# EEZ_DIB_BP3C_r1B5.net
KiCad netlist of a schematic drawn in EAGLE
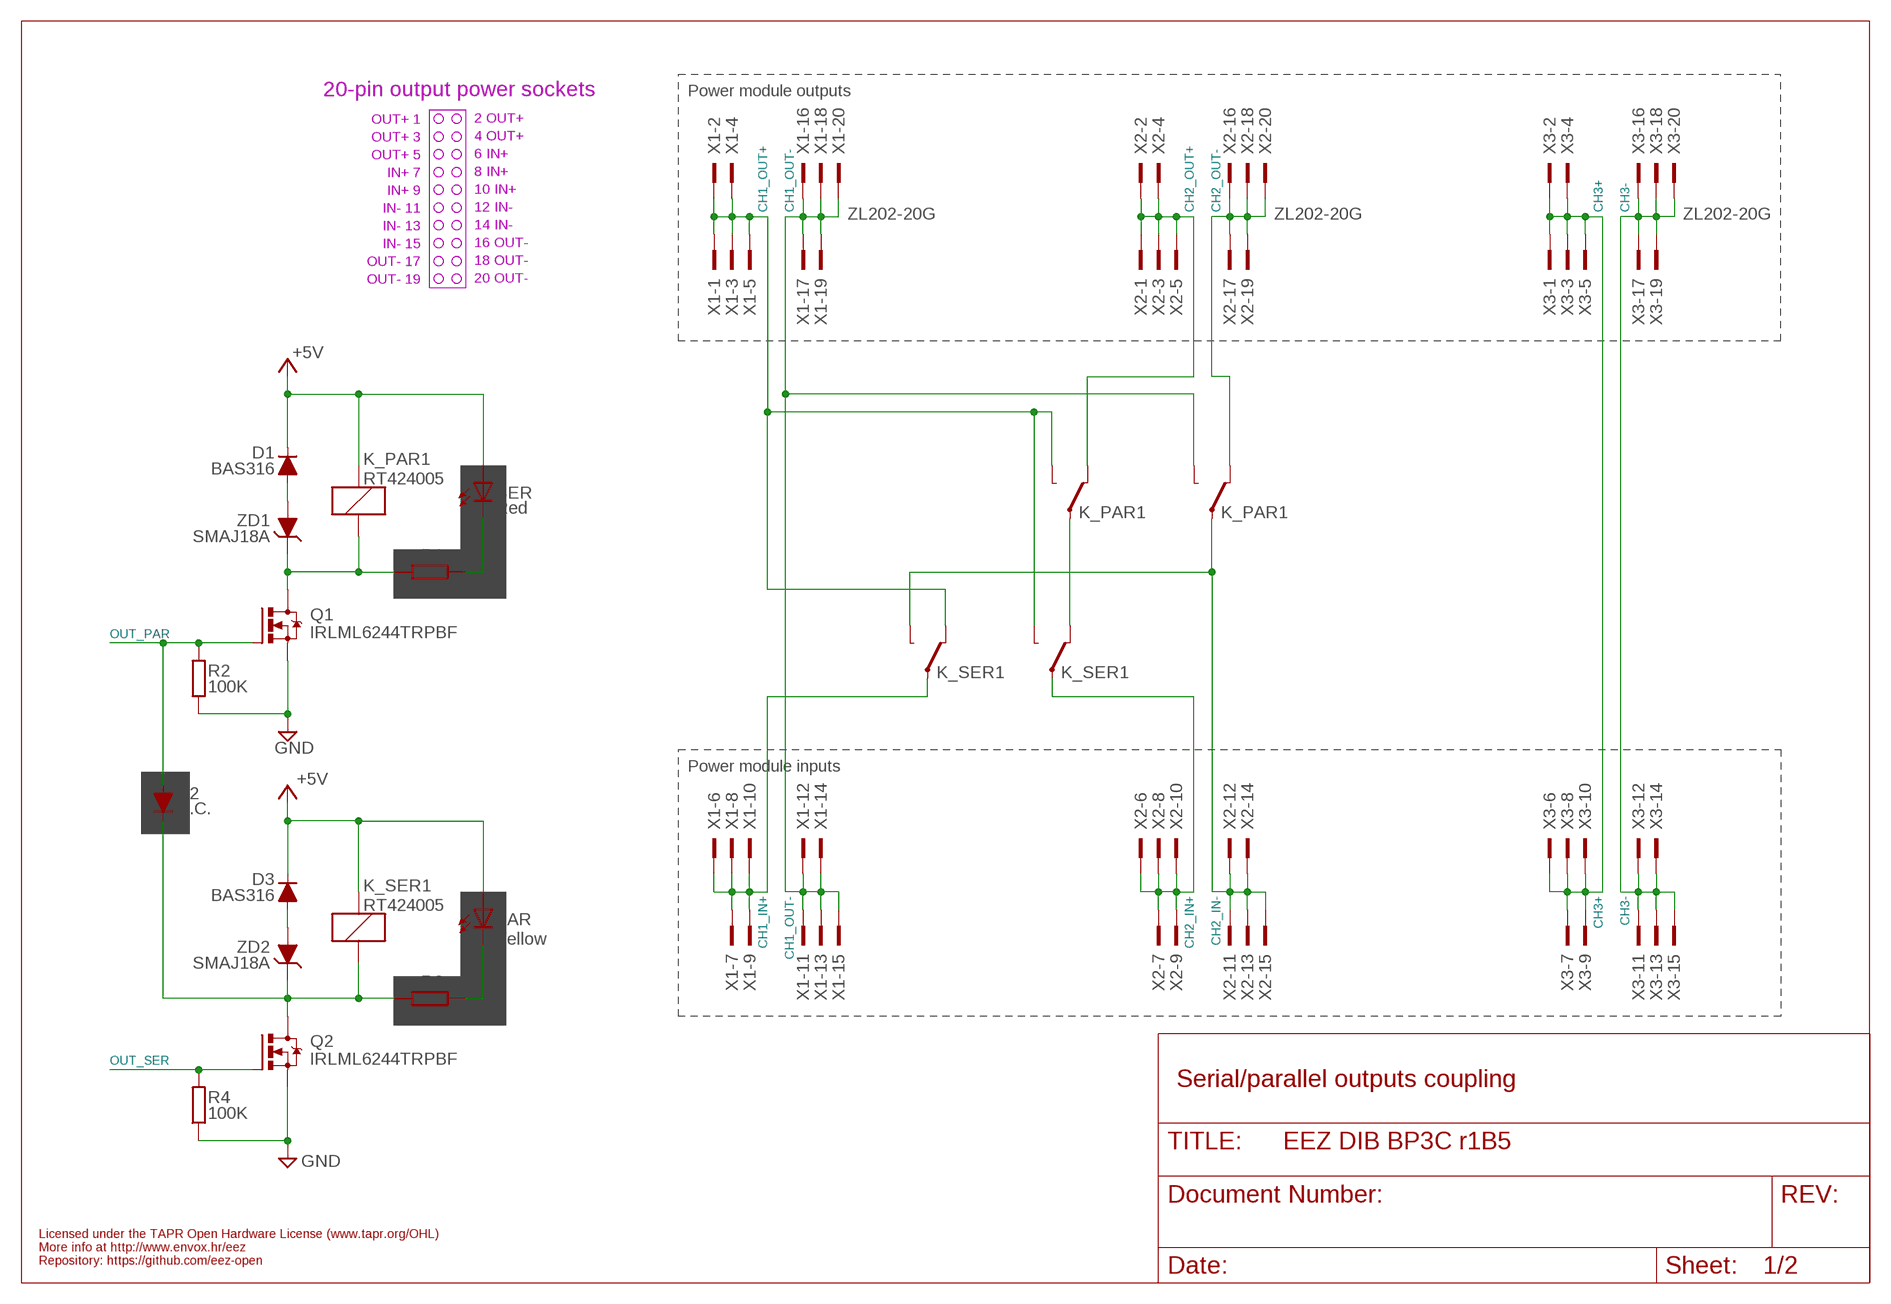
[diagram p0: schematic, sheet 1]
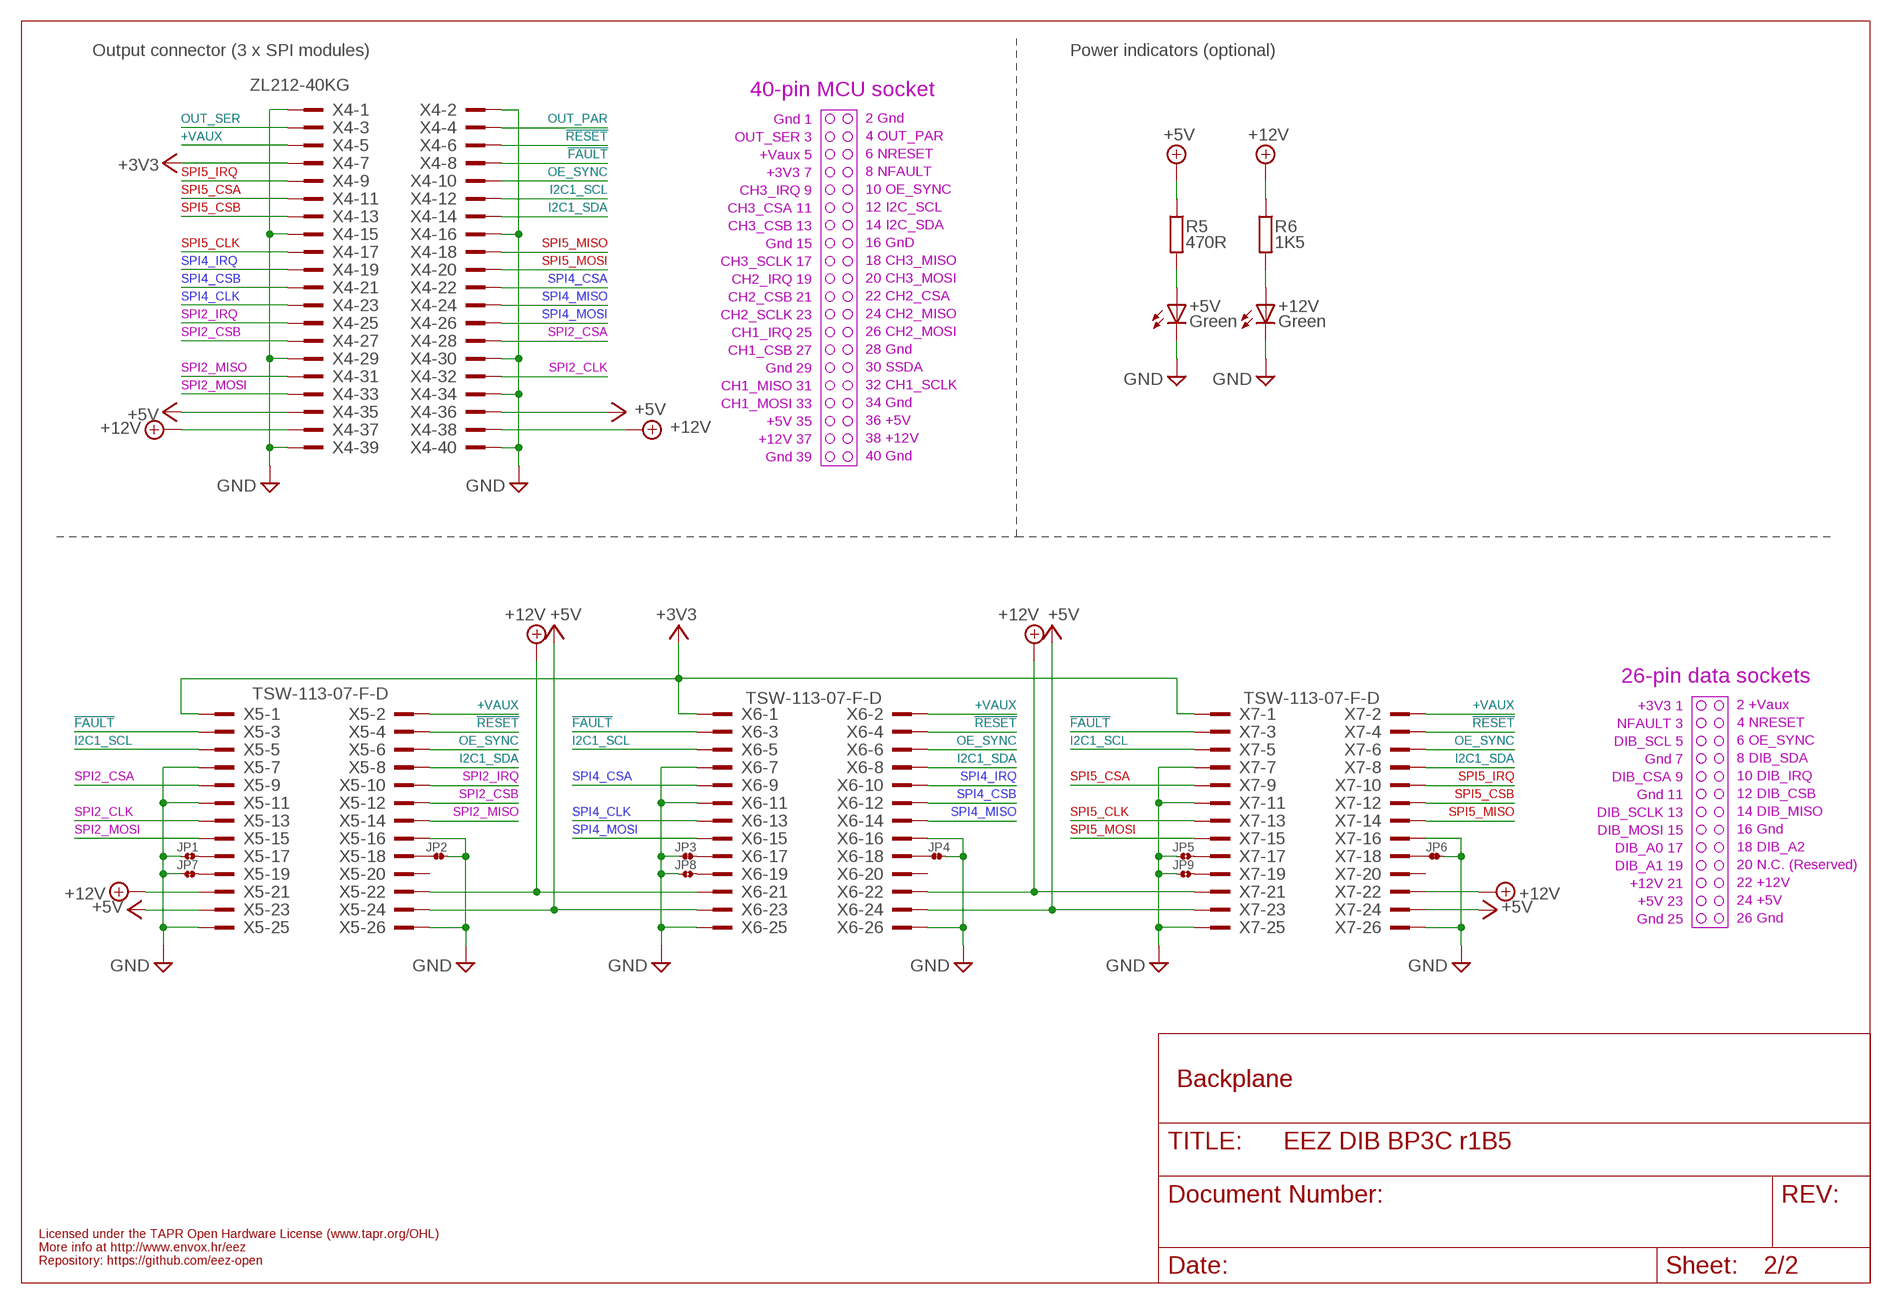
[diagram p1: schematic, sheet 2]

(export (version "E")
  (design (tool "Eeschema 10.0.6"))
  (components
    (comp (ref "D1")
      (value "BAS316")
      (footprint "eagle-import:SOD323-R")
      (libsource (lib "eagle-import") (part "DIODESOD323R"))
    )
    (comp (ref "D2")
      (value "N.C.")
      (footprint "eagle-import:SOD323-R")
      (libsource (lib "eagle-import") (part "DIODESOD323R"))
    )
    (comp (ref "D3")
      (value "BAS316")
      (footprint "eagle-import:SOD323-R")
      (libsource (lib "eagle-import") (part "DIODESOD323R"))
    )
    (comp (ref "K_PAR1")
      (value "RT424005")
      (footprint "eagle-import:RT-C_016A5_ROUND")
      (libsource (lib "eagle-import") (part "RELAY_RT314012-2"))
    )
    (comp (ref "K_SER1")
      (value "RT424005")
      (footprint "eagle-import:RT-C_016A5_ROUND")
      (libsource (lib "eagle-import") (part "RELAY_RT314012-2"))
    )
    (comp (ref "PAR")
      (value "Yellow")
      (footprint "eagle-import:LED_0805")
      (libsource (lib "eagle-import") (part "LED0805"))
    )
    (comp (ref "Q1")
      (value "IRLML6244TRPBF")
      (footprint "eagle-import:SOT103P240X110-3N")
      (fields
        (field (name "MPN") "2N7002-7-F")
        (field (name "MPN_1") "2N7002-7-F")
        (field (name "OC_FARNELL") "1713823")
        (field (name "OC_NEWARK") "25R5679")
        (field (name "PACKAGE") "SOT-23-3")
        (field (name "SUPPLIER") "DIODES INC.")
      )
      (libsource (lib "eagle-import") (part "2N7002"))
    )
    (comp (ref "Q2")
      (value "IRLML6244TRPBF")
      (footprint "eagle-import:SOT103P240X110-3N")
      (fields
        (field (name "MPN") "2N7002-7-F")
        (field (name "MPN_1") "2N7002-7-F")
        (field (name "OC_FARNELL") "1713823")
        (field (name "OC_NEWARK") "25R5679")
        (field (name "PACKAGE") "SOT-23-3")
        (field (name "SUPPLIER") "DIODES INC.")
      )
      (libsource (lib "eagle-import") (part "2N7002"))
    )
    (comp (ref "R1")
      (value "330R")
      (footprint "eagle-import:R0805")
      (libsource (lib "eagle-import") (part "R-EU_R0805"))
    )
    (comp (ref "R2")
      (value "100K")
      (footprint "eagle-import:R0805")
      (libsource (lib "eagle-import") (part "R-EU_R0805"))
    )
    (comp (ref "R3")
      (value "330R")
      (footprint "eagle-import:R0805")
      (libsource (lib "eagle-import") (part "R-EU_R0805"))
    )
    (comp (ref "R4")
      (value "100K")
      (footprint "eagle-import:R0805")
      (libsource (lib "eagle-import") (part "R-EU_R0805"))
    )
    (comp (ref "SER")
      (value "Red")
      (footprint "eagle-import:LED_0805")
      (libsource (lib "eagle-import") (part "LED0805"))
    )
    (comp (ref "X1")
      (value "ZL202-20G")
      (footprint "eagle-import:DS1021-2_10SF11")
      (libsource (lib "eagle-import") (part "DS1021-210SF11"))
    )
    (comp (ref "X2")
      (value "ZL202-20G")
      (footprint "eagle-import:DS1021-2_10SF11")
      (libsource (lib "eagle-import") (part "DS1021-210SF11"))
    )
    (comp (ref "X3")
      (value "ZL202-20G")
      (footprint "eagle-import:DS1021-2_10SF11")
      (libsource (lib "eagle-import") (part "DS1021-210SF11"))
    )
    (comp (ref "ZD1")
      (value "SMAJ18A")
      (footprint "eagle-import:DO214AC")
      (libsource (lib "eagle-import") (part "PSMAXX"))
    )
    (comp (ref "ZD2")
      (value "SMAJ18A")
      (footprint "eagle-import:DO214AC")
      (libsource (lib "eagle-import") (part "PSMAXX"))
    )
    (comp (ref "+5V")
      (value "Green")
      (footprint "eagle-import:LED_0805")
      (libsource (lib "eagle-import") (part "LED0805"))
    )
    (comp (ref "+12V")
      (value "Green")
      (footprint "eagle-import:LED_0805")
      (libsource (lib "eagle-import") (part "LED0805"))
    )
    (comp (ref "JP1")
      (value "JP2-CUT")
      (footprint "eagle-import:JP2-CUT")
      (libsource (lib "eagle-import") (part "JP2-CUT"))
    )
    (comp (ref "JP2")
      (value "JP2-NOCUT")
      (footprint "eagle-import:JP2-NOCUT")
      (libsource (lib "eagle-import") (part "JP2-NOCUT"))
    )
    (comp (ref "JP3")
      (value "JP2-NOCUT")
      (footprint "eagle-import:JP2-NOCUT")
      (libsource (lib "eagle-import") (part "JP2-NOCUT"))
    )
    (comp (ref "JP4")
      (value "JP2-NOCUT")
      (footprint "eagle-import:JP2-NOCUT")
      (libsource (lib "eagle-import") (part "JP2-NOCUT"))
    )
    (comp (ref "JP5")
      (value "JP2-CUT")
      (footprint "eagle-import:JP2-CUT")
      (libsource (lib "eagle-import") (part "JP2-CUT"))
    )
    (comp (ref "JP6")
      (value "JP2-NOCUT")
      (footprint "eagle-import:JP2-NOCUT")
      (libsource (lib "eagle-import") (part "JP2-NOCUT"))
    )
    (comp (ref "JP7")
      (value "JP2-NOCUT")
      (footprint "eagle-import:JP2-NOCUT")
      (libsource (lib "eagle-import") (part "JP2-NOCUT"))
    )
    (comp (ref "JP8")
      (value "JP2-CUT")
      (footprint "eagle-import:JP2-CUT")
      (libsource (lib "eagle-import") (part "JP2-CUT"))
    )
    (comp (ref "JP9")
      (value "JP2-CUT")
      (footprint "eagle-import:JP2-CUT")
      (libsource (lib "eagle-import") (part "JP2-CUT"))
    )
    (comp (ref "R5")
      (value "470R")
      (footprint "eagle-import:R0805")
      (libsource (lib "eagle-import") (part "R-EU_R0805"))
    )
    (comp (ref "R6")
      (value "1K5")
      (footprint "eagle-import:R0805")
      (libsource (lib "eagle-import") (part "R-EU_R0805"))
    )
    (comp (ref "X4")
      (value "ZL212-40KG")
      (footprint "eagle-import:ZL212-40KG")
      (libsource (lib "eagle-import") (part "ZL212-40KG"))
    )
    (comp (ref "X5")
      (value "TSW-113-07-F-D")
      (footprint "eagle-import:TSW-113-07-F-D")
      (libsource (lib "eagle-import") (part "TSW-113-07-F-D"))
    )
    (comp (ref "X6")
      (value "TSW-113-07-F-D")
      (footprint "eagle-import:TSW-113-07-F-D")
      (libsource (lib "eagle-import") (part "TSW-113-07-F-D"))
    )
    (comp (ref "X7")
      (value "TSW-113-07-F-D")
      (footprint "eagle-import:TSW-113-07-F-D")
      (libsource (lib "eagle-import") (part "TSW-113-07-F-D"))
    )
  )
  (nets
    (net (code "1") (name "+3V3") (class "Default")
      (node (ref "X4") (pin "7") (pinfunction "1_7") (pintype "passive"))
      (node (ref "X5") (pin "1") (pinfunction "1_1") (pintype "passive"))
      (node (ref "X6") (pin "1") (pinfunction "1_1") (pintype "passive"))
      (node (ref "X7") (pin "1") (pinfunction "1_1") (pintype "passive"))
    )
    (net (code "2") (name "+5V") (class "Default")
      (node (ref "D1") (pin "C") (pinfunction "C_C") (pintype "passive"))
      (node (ref "D3") (pin "C") (pinfunction "C_C") (pintype "passive"))
      (node (ref "K_PAR1") (pin "A2") (pinfunction "C1_A2") (pintype "passive"))
      (node (ref "K_SER1") (pin "A2") (pinfunction "C1_A2") (pintype "passive"))
      (node (ref "PAR") (pin "A") (pinfunction "A_A") (pintype "passive"))
      (node (ref "R5") (pin "1") (pinfunction "1_1") (pintype "passive"))
      (node (ref "SER") (pin "A") (pinfunction "A_A") (pintype "passive"))
      (node (ref "X4") (pin "35") (pinfunction "1_35") (pintype "passive"))
      (node (ref "X4") (pin "36") (pinfunction "1_36") (pintype "passive"))
      (node (ref "X5") (pin "23") (pinfunction "1_23") (pintype "passive"))
      (node (ref "X5") (pin "24") (pinfunction "1_24") (pintype "passive"))
      (node (ref "X6") (pin "23") (pinfunction "1_23") (pintype "passive"))
      (node (ref "X6") (pin "24") (pinfunction "1_24") (pintype "passive"))
      (node (ref "X7") (pin "23") (pinfunction "1_23") (pintype "passive"))
      (node (ref "X7") (pin "24") (pinfunction "1_24") (pintype "passive"))
    )
    (net (code "3") (name "+12V") (class "Default")
      (node (ref "R6") (pin "1") (pinfunction "1_1") (pintype "passive"))
      (node (ref "X4") (pin "37") (pinfunction "1_37") (pintype "passive"))
      (node (ref "X4") (pin "38") (pinfunction "1_38") (pintype "passive"))
      (node (ref "X5") (pin "21") (pinfunction "1_21") (pintype "passive"))
      (node (ref "X5") (pin "22") (pinfunction "1_22") (pintype "passive"))
      (node (ref "X6") (pin "21") (pinfunction "1_21") (pintype "passive"))
      (node (ref "X6") (pin "22") (pinfunction "1_22") (pintype "passive"))
      (node (ref "X7") (pin "21") (pinfunction "1_21") (pintype "passive"))
      (node (ref "X7") (pin "22") (pinfunction "1_22") (pintype "passive"))
    )
    (net (code "4") (name "+VAUX") (class "Default")
      (node (ref "X4") (pin "5") (pinfunction "1_5") (pintype "passive"))
      (node (ref "X5") (pin "2") (pinfunction "1_2") (pintype "passive"))
      (node (ref "X6") (pin "2") (pinfunction "1_2") (pintype "passive"))
      (node (ref "X7") (pin "2") (pinfunction "1_2") (pintype "passive"))
    )
    (net (code "5") (name "CH1_IN+") (class "Default")
      (node (ref "K_SER1") (pin "11A") (pinfunction "P_11A") (pintype "passive"))
      (node (ref "X1") (pin "10") (pinfunction "1_10") (pintype "passive"))
      (node (ref "X1") (pin "6") (pinfunction "1_6") (pintype "passive"))
      (node (ref "X1") (pin "7") (pinfunction "1_7") (pintype "passive"))
      (node (ref "X1") (pin "8") (pinfunction "1_8") (pintype "passive"))
      (node (ref "X1") (pin "9") (pinfunction "1_9") (pintype "passive"))
    )
    (net (code "6") (name "CH1_OUT+") (class "Default")
      (node (ref "K_PAR1") (pin "14A") (pinfunction "O_14A") (pintype "passive"))
      (node (ref "K_SER1") (pin "12A") (pinfunction "S_12A") (pintype "passive"))
      (node (ref "K_SER1") (pin "14B") (pinfunction "O_14B") (pintype "passive"))
      (node (ref "X1") (pin "1") (pinfunction "1_1") (pintype "passive"))
      (node (ref "X1") (pin "2") (pinfunction "1_2") (pintype "passive"))
      (node (ref "X1") (pin "3") (pinfunction "1_3") (pintype "passive"))
      (node (ref "X1") (pin "4") (pinfunction "1_4") (pintype "passive"))
      (node (ref "X1") (pin "5") (pinfunction "1_5") (pintype "passive"))
    )
    (net (code "7") (name "CH1_OUT-") (class "Default")
      (node (ref "K_PAR1") (pin "14B") (pinfunction "O_14B") (pintype "passive"))
      (node (ref "X1") (pin "11") (pinfunction "1_11") (pintype "passive"))
      (node (ref "X1") (pin "12") (pinfunction "1_12") (pintype "passive"))
      (node (ref "X1") (pin "13") (pinfunction "1_13") (pintype "passive"))
      (node (ref "X1") (pin "14") (pinfunction "1_14") (pintype "passive"))
      (node (ref "X1") (pin "15") (pinfunction "1_15") (pintype "passive"))
      (node (ref "X1") (pin "16") (pinfunction "1_16") (pintype "passive"))
      (node (ref "X1") (pin "17") (pinfunction "1_17") (pintype "passive"))
      (node (ref "X1") (pin "18") (pinfunction "1_18") (pintype "passive"))
      (node (ref "X1") (pin "19") (pinfunction "1_19") (pintype "passive"))
      (node (ref "X1") (pin "20") (pinfunction "1_20") (pintype "passive"))
    )
    (net (code "8") (name "CH2_IN+") (class "Default")
      (node (ref "K_SER1") (pin "11B") (pinfunction "P_11B") (pintype "passive"))
      (node (ref "X2") (pin "10") (pinfunction "1_10") (pintype "passive"))
      (node (ref "X2") (pin "6") (pinfunction "1_6") (pintype "passive"))
      (node (ref "X2") (pin "7") (pinfunction "1_7") (pintype "passive"))
      (node (ref "X2") (pin "8") (pinfunction "1_8") (pintype "passive"))
      (node (ref "X2") (pin "9") (pinfunction "1_9") (pintype "passive"))
    )
    (net (code "9") (name "CH2_IN-") (class "Default")
      (node (ref "K_PAR1") (pin "11B") (pinfunction "P_11B") (pintype "passive"))
      (node (ref "K_SER1") (pin "14A") (pinfunction "O_14A") (pintype "passive"))
      (node (ref "X2") (pin "11") (pinfunction "1_11") (pintype "passive"))
      (node (ref "X2") (pin "12") (pinfunction "1_12") (pintype "passive"))
      (node (ref "X2") (pin "13") (pinfunction "1_13") (pintype "passive"))
      (node (ref "X2") (pin "14") (pinfunction "1_14") (pintype "passive"))
      (node (ref "X2") (pin "15") (pinfunction "1_15") (pintype "passive"))
    )
    (net (code "10") (name "CH2_OUT+") (class "Default")
      (node (ref "K_PAR1") (pin "12A") (pinfunction "S_12A") (pintype "passive"))
      (node (ref "X2") (pin "1") (pinfunction "1_1") (pintype "passive"))
      (node (ref "X2") (pin "2") (pinfunction "1_2") (pintype "passive"))
      (node (ref "X2") (pin "3") (pinfunction "1_3") (pintype "passive"))
      (node (ref "X2") (pin "4") (pinfunction "1_4") (pintype "passive"))
      (node (ref "X2") (pin "5") (pinfunction "1_5") (pintype "passive"))
    )
    (net (code "11") (name "CH2_OUT-") (class "Default")
      (node (ref "K_PAR1") (pin "12B") (pinfunction "S_12B") (pintype "passive"))
      (node (ref "X2") (pin "16") (pinfunction "1_16") (pintype "passive"))
      (node (ref "X2") (pin "17") (pinfunction "1_17") (pintype "passive"))
      (node (ref "X2") (pin "18") (pinfunction "1_18") (pintype "passive"))
      (node (ref "X2") (pin "19") (pinfunction "1_19") (pintype "passive"))
      (node (ref "X2") (pin "20") (pinfunction "1_20") (pintype "passive"))
    )
    (net (code "12") (name "CH3+") (class "Default")
      (node (ref "X3") (pin "1") (pinfunction "1_1") (pintype "passive"))
      (node (ref "X3") (pin "10") (pinfunction "1_10") (pintype "passive"))
      (node (ref "X3") (pin "2") (pinfunction "1_2") (pintype "passive"))
      (node (ref "X3") (pin "3") (pinfunction "1_3") (pintype "passive"))
      (node (ref "X3") (pin "4") (pinfunction "1_4") (pintype "passive"))
      (node (ref "X3") (pin "5") (pinfunction "1_5") (pintype "passive"))
      (node (ref "X3") (pin "6") (pinfunction "1_6") (pintype "passive"))
      (node (ref "X3") (pin "7") (pinfunction "1_7") (pintype "passive"))
      (node (ref "X3") (pin "8") (pinfunction "1_8") (pintype "passive"))
      (node (ref "X3") (pin "9") (pinfunction "1_9") (pintype "passive"))
    )
    (net (code "13") (name "CH3-") (class "Default")
      (node (ref "X3") (pin "11") (pinfunction "1_11") (pintype "passive"))
      (node (ref "X3") (pin "12") (pinfunction "1_12") (pintype "passive"))
      (node (ref "X3") (pin "13") (pinfunction "1_13") (pintype "passive"))
      (node (ref "X3") (pin "14") (pinfunction "1_14") (pintype "passive"))
      (node (ref "X3") (pin "15") (pinfunction "1_15") (pintype "passive"))
      (node (ref "X3") (pin "16") (pinfunction "1_16") (pintype "passive"))
      (node (ref "X3") (pin "17") (pinfunction "1_17") (pintype "passive"))
      (node (ref "X3") (pin "18") (pinfunction "1_18") (pintype "passive"))
      (node (ref "X3") (pin "19") (pinfunction "1_19") (pintype "passive"))
      (node (ref "X3") (pin "20") (pinfunction "1_20") (pintype "passive"))
    )
    (net (code "14") (name "GND") (class "Default")
      (node (ref "+12V") (pin "C") (pinfunction "C_C") (pintype "passive"))
      (node (ref "+5V") (pin "C") (pinfunction "C_C") (pintype "passive"))
      (node (ref "JP1") (pin "1") (pinfunction "1_1") (pintype "passive"))
      (node (ref "JP2") (pin "2") (pinfunction "2_2") (pintype "passive"))
      (node (ref "JP3") (pin "1") (pinfunction "1_1") (pintype "passive"))
      (node (ref "JP4") (pin "2") (pinfunction "2_2") (pintype "passive"))
      (node (ref "JP5") (pin "1") (pinfunction "1_1") (pintype "passive"))
      (node (ref "JP6") (pin "2") (pinfunction "2_2") (pintype "passive"))
      (node (ref "JP7") (pin "1") (pinfunction "1_1") (pintype "passive"))
      (node (ref "JP8") (pin "1") (pinfunction "1_1") (pintype "passive"))
      (node (ref "JP9") (pin "1") (pinfunction "1_1") (pintype "passive"))
      (node (ref "Q1") (pin "2") (pinfunction "S_2") (pintype "passive"))
      (node (ref "Q2") (pin "2") (pinfunction "S_2") (pintype "passive"))
      (node (ref "R2") (pin "1") (pinfunction "1_1") (pintype "passive"))
      (node (ref "R4") (pin "1") (pinfunction "1_1") (pintype "passive"))
      (node (ref "X4") (pin "1") (pinfunction "1_1") (pintype "passive"))
      (node (ref "X4") (pin "15") (pinfunction "1_15") (pintype "passive"))
      (node (ref "X4") (pin "16") (pinfunction "1_16") (pintype "passive"))
      (node (ref "X4") (pin "2") (pinfunction "1_2") (pintype "passive"))
      (node (ref "X4") (pin "29") (pinfunction "1_29") (pintype "passive"))
      (node (ref "X4") (pin "30") (pinfunction "1_30") (pintype "passive"))
      (node (ref "X4") (pin "34") (pinfunction "1_34") (pintype "passive"))
      (node (ref "X4") (pin "39") (pinfunction "1_39") (pintype "passive"))
      (node (ref "X4") (pin "40") (pinfunction "1_40") (pintype "passive"))
      (node (ref "X5") (pin "11") (pinfunction "1_11") (pintype "passive"))
      (node (ref "X5") (pin "16") (pinfunction "1_16") (pintype "passive"))
      (node (ref "X5") (pin "25") (pinfunction "1_25") (pintype "passive"))
      (node (ref "X5") (pin "26") (pinfunction "1_26") (pintype "passive"))
      (node (ref "X5") (pin "7") (pinfunction "1_7") (pintype "passive"))
      (node (ref "X6") (pin "11") (pinfunction "1_11") (pintype "passive"))
      (node (ref "X6") (pin "16") (pinfunction "1_16") (pintype "passive"))
      (node (ref "X6") (pin "25") (pinfunction "1_25") (pintype "passive"))
      (node (ref "X6") (pin "26") (pinfunction "1_26") (pintype "passive"))
      (node (ref "X6") (pin "7") (pinfunction "1_7") (pintype "passive"))
      (node (ref "X7") (pin "11") (pinfunction "1_11") (pintype "passive"))
      (node (ref "X7") (pin "16") (pinfunction "1_16") (pintype "passive"))
      (node (ref "X7") (pin "25") (pinfunction "1_25") (pintype "passive"))
      (node (ref "X7") (pin "26") (pinfunction "1_26") (pintype "passive"))
      (node (ref "X7") (pin "7") (pinfunction "1_7") (pintype "passive"))
    )
    (net (code "15") (name "I2C1_SCL") (class "Default")
      (node (ref "X4") (pin "12") (pinfunction "1_12") (pintype "passive"))
      (node (ref "X5") (pin "5") (pinfunction "1_5") (pintype "passive"))
      (node (ref "X6") (pin "5") (pinfunction "1_5") (pintype "passive"))
      (node (ref "X7") (pin "5") (pinfunction "1_5") (pintype "passive"))
    )
    (net (code "16") (name "I2C1_SDA") (class "Default")
      (node (ref "X4") (pin "14") (pinfunction "1_14") (pintype "passive"))
      (node (ref "X5") (pin "8") (pinfunction "1_8") (pintype "passive"))
      (node (ref "X6") (pin "8") (pinfunction "1_8") (pintype "passive"))
      (node (ref "X7") (pin "8") (pinfunction "1_8") (pintype "passive"))
    )
    (net (code "17") (name "Net-(+5V-PadA)") (class "Default")
      (node (ref "+5V") (pin "A") (pinfunction "A_A") (pintype "passive"))
      (node (ref "R5") (pin "2") (pinfunction "2_2") (pintype "passive"))
    )
    (net (code "18") (name "Net-(+12V-PadA)") (class "Default")
      (node (ref "+12V") (pin "A") (pinfunction "A_A") (pintype "passive"))
      (node (ref "R6") (pin "2") (pinfunction "2_2") (pintype "passive"))
    )
    (net (code "19") (name "Net-(D1-PadA)") (class "Default")
      (node (ref "D1") (pin "A") (pinfunction "A_A") (pintype "passive"))
      (node (ref "ZD1") (pin "A") (pinfunction "A_A") (pintype "passive"))
    )
    (net (code "20") (name "Net-(D3-PadA)") (class "Default")
      (node (ref "D3") (pin "A") (pinfunction "A_A") (pintype "passive"))
      (node (ref "ZD2") (pin "A") (pinfunction "A_A") (pintype "passive"))
    )
    (net (code "21") (name "Net-(K_PAR1A-P)") (class "Default")
      (node (ref "K_PAR1") (pin "11A") (pinfunction "P_11A") (pintype "passive"))
      (node (ref "K_SER1") (pin "12B") (pinfunction "S_12B") (pintype "passive"))
    )
    (net (code "22") (name "Net-(K_PAR1C-C2)") (class "Default")
      (node (ref "K_PAR1") (pin "A1") (pinfunction "C2_A1") (pintype "passive"))
      (node (ref "Q1") (pin "3") (pinfunction "D_3") (pintype "passive"))
      (node (ref "R1") (pin "2") (pinfunction "2_2") (pintype "passive"))
      (node (ref "ZD1") (pin "C") (pinfunction "C_C") (pintype "passive"))
    )
    (net (code "23") (name "Net-(K_SER1C-C2)") (class "Default")
      (node (ref "D2") (pin "C") (pinfunction "C_C") (pintype "passive"))
      (node (ref "K_SER1") (pin "A1") (pinfunction "C2_A1") (pintype "passive"))
      (node (ref "Q2") (pin "3") (pinfunction "D_3") (pintype "passive"))
      (node (ref "R3") (pin "2") (pinfunction "2_2") (pintype "passive"))
      (node (ref "ZD2") (pin "C") (pinfunction "C_C") (pintype "passive"))
    )
    (net (code "24") (name "Net-(PAR-PadC)") (class "Default")
      (node (ref "PAR") (pin "C") (pinfunction "C_C") (pintype "passive"))
      (node (ref "R3") (pin "1") (pinfunction "1_1") (pintype "passive"))
    )
    (net (code "25") (name "Net-(R1-Pad1)") (class "Default")
      (node (ref "R1") (pin "1") (pinfunction "1_1") (pintype "passive"))
      (node (ref "SER") (pin "C") (pinfunction "C_C") (pintype "passive"))
    )
    (net (code "26") (name "Net-(X5I-1)") (class "Default")
      (node (ref "JP1") (pin "2") (pinfunction "2_2") (pintype "passive"))
      (node (ref "X5") (pin "17") (pinfunction "1_17") (pintype "passive"))
    )
    (net (code "27") (name "Net-(X5J-1)") (class "Default")
      (node (ref "JP2") (pin "1") (pinfunction "1_1") (pintype "passive"))
      (node (ref "X5") (pin "18") (pinfunction "1_18") (pintype "passive"))
    )
    (net (code "28") (name "Net-(X5K-1)") (class "Default")
      (node (ref "JP7") (pin "2") (pinfunction "2_2") (pintype "passive"))
      (node (ref "X5") (pin "19") (pinfunction "1_19") (pintype "passive"))
    )
    (net (code "29") (name "Net-(X6I-1)") (class "Default")
      (node (ref "JP3") (pin "2") (pinfunction "2_2") (pintype "passive"))
      (node (ref "X6") (pin "17") (pinfunction "1_17") (pintype "passive"))
    )
    (net (code "30") (name "Net-(X6J-1)") (class "Default")
      (node (ref "JP4") (pin "1") (pinfunction "1_1") (pintype "passive"))
      (node (ref "X6") (pin "18") (pinfunction "1_18") (pintype "passive"))
    )
    (net (code "31") (name "Net-(X6K-1)") (class "Default")
      (node (ref "JP8") (pin "2") (pinfunction "2_2") (pintype "passive"))
      (node (ref "X6") (pin "19") (pinfunction "1_19") (pintype "passive"))
    )
    (net (code "32") (name "Net-(X7I-1)") (class "Default")
      (node (ref "JP5") (pin "2") (pinfunction "2_2") (pintype "passive"))
      (node (ref "X7") (pin "17") (pinfunction "1_17") (pintype "passive"))
    )
    (net (code "33") (name "Net-(X7J-1)") (class "Default")
      (node (ref "JP6") (pin "1") (pinfunction "1_1") (pintype "passive"))
      (node (ref "X7") (pin "18") (pinfunction "1_18") (pintype "passive"))
    )
    (net (code "34") (name "Net-(X7K-1)") (class "Default")
      (node (ref "JP9") (pin "2") (pinfunction "2_2") (pintype "passive"))
      (node (ref "X7") (pin "19") (pinfunction "1_19") (pintype "passive"))
    )
    (net (code "35") (name "OE_SYNC") (class "Default")
      (node (ref "X4") (pin "10") (pinfunction "1_10") (pintype "passive"))
      (node (ref "X5") (pin "6") (pinfunction "1_6") (pintype "passive"))
      (node (ref "X6") (pin "6") (pinfunction "1_6") (pintype "passive"))
      (node (ref "X7") (pin "6") (pinfunction "1_6") (pintype "passive"))
    )
    (net (code "36") (name "OUT_PAR") (class "Default")
      (node (ref "D2") (pin "A") (pinfunction "A_A") (pintype "passive"))
      (node (ref "Q1") (pin "1") (pinfunction "G_1") (pintype "passive"))
      (node (ref "R2") (pin "2") (pinfunction "2_2") (pintype "passive"))
      (node (ref "X4") (pin "4") (pinfunction "1_4") (pintype "passive"))
    )
    (net (code "37") (name "OUT_SER") (class "Default")
      (node (ref "Q2") (pin "1") (pinfunction "G_1") (pintype "passive"))
      (node (ref "R4") (pin "2") (pinfunction "2_2") (pintype "passive"))
      (node (ref "X4") (pin "3") (pinfunction "1_3") (pintype "passive"))
    )
    (net (code "38") (name "SPI2_CLK") (class "Default")
      (node (ref "X4") (pin "32") (pinfunction "1_32") (pintype "passive"))
      (node (ref "X5") (pin "13") (pinfunction "1_13") (pintype "passive"))
    )
    (net (code "39") (name "SPI2_CSA") (class "Default")
      (node (ref "X4") (pin "28") (pinfunction "1_28") (pintype "passive"))
      (node (ref "X5") (pin "9") (pinfunction "1_9") (pintype "passive"))
    )
    (net (code "40") (name "SPI2_CSB") (class "Default")
      (node (ref "X4") (pin "27") (pinfunction "1_27") (pintype "passive"))
      (node (ref "X5") (pin "12") (pinfunction "1_12") (pintype "passive"))
    )
    (net (code "41") (name "SPI2_IRQ") (class "Default")
      (node (ref "X4") (pin "25") (pinfunction "1_25") (pintype "passive"))
      (node (ref "X5") (pin "10") (pinfunction "1_10") (pintype "passive"))
    )
    (net (code "42") (name "SPI2_MISO") (class "Default")
      (node (ref "X4") (pin "31") (pinfunction "1_31") (pintype "passive"))
      (node (ref "X5") (pin "14") (pinfunction "1_14") (pintype "passive"))
    )
    (net (code "43") (name "SPI2_MOSI") (class "Default")
      (node (ref "X4") (pin "33") (pinfunction "1_33") (pintype "passive"))
      (node (ref "X5") (pin "15") (pinfunction "1_15") (pintype "passive"))
    )
    (net (code "44") (name "SPI4_CLK") (class "Default")
      (node (ref "X4") (pin "23") (pinfunction "1_23") (pintype "passive"))
      (node (ref "X6") (pin "13") (pinfunction "1_13") (pintype "passive"))
    )
    (net (code "45") (name "SPI4_CSA") (class "Default")
      (node (ref "X4") (pin "22") (pinfunction "1_22") (pintype "passive"))
      (node (ref "X6") (pin "9") (pinfunction "1_9") (pintype "passive"))
    )
    (net (code "46") (name "SPI4_CSB") (class "Default")
      (node (ref "X4") (pin "21") (pinfunction "1_21") (pintype "passive"))
      (node (ref "X6") (pin "12") (pinfunction "1_12") (pintype "passive"))
    )
    (net (code "47") (name "SPI4_IRQ") (class "Default")
      (node (ref "X4") (pin "19") (pinfunction "1_19") (pintype "passive"))
      (node (ref "X6") (pin "10") (pinfunction "1_10") (pintype "passive"))
    )
    (net (code "48") (name "SPI4_MISO") (class "Default")
      (node (ref "X4") (pin "24") (pinfunction "1_24") (pintype "passive"))
      (node (ref "X6") (pin "14") (pinfunction "1_14") (pintype "passive"))
    )
    (net (code "49") (name "SPI4_MOSI") (class "Default")
      (node (ref "X4") (pin "26") (pinfunction "1_26") (pintype "passive"))
      (node (ref "X6") (pin "15") (pinfunction "1_15") (pintype "passive"))
    )
    (net (code "50") (name "SPI5_CLK") (class "Default")
      (node (ref "X4") (pin "17") (pinfunction "1_17") (pintype "passive"))
      (node (ref "X7") (pin "13") (pinfunction "1_13") (pintype "passive"))
    )
    (net (code "51") (name "SPI5_CSA") (class "Default")
      (node (ref "X4") (pin "11") (pinfunction "1_11") (pintype "passive"))
      (node (ref "X7") (pin "9") (pinfunction "1_9") (pintype "passive"))
    )
    (net (code "52") (name "SPI5_CSB") (class "Default")
      (node (ref "X4") (pin "13") (pinfunction "1_13") (pintype "passive"))
      (node (ref "X7") (pin "12") (pinfunction "1_12") (pintype "passive"))
    )
    (net (code "53") (name "SPI5_IRQ") (class "Default")
      (node (ref "X4") (pin "9") (pinfunction "1_9") (pintype "passive"))
      (node (ref "X7") (pin "10") (pinfunction "1_10") (pintype "passive"))
    )
    (net (code "54") (name "SPI5_MISO") (class "Default")
      (node (ref "X4") (pin "18") (pinfunction "1_18") (pintype "passive"))
      (node (ref "X7") (pin "14") (pinfunction "1_14") (pintype "passive"))
    )
    (net (code "55") (name "SPI5_MOSI") (class "Default")
      (node (ref "X4") (pin "20") (pinfunction "1_20") (pintype "passive"))
      (node (ref "X7") (pin "15") (pinfunction "1_15") (pintype "passive"))
    )
    (net (code "56") (name "unconnected-(X5M-1-Pad20)") (class "Default")
      (node (ref "X5") (pin "20") (pinfunction "1_20") (pintype "passive"))
    )
    (net (code "57") (name "unconnected-(X6M-1-Pad20)") (class "Default")
      (node (ref "X6") (pin "20") (pinfunction "1_20") (pintype "passive"))
    )
    (net (code "58") (name "unconnected-(X7M-1-Pad20)") (class "Default")
      (node (ref "X7") (pin "20") (pinfunction "1_20") (pintype "passive"))
    )
    (net (code "59") (name "~{FAULT}") (class "Default")
      (node (ref "X4") (pin "8") (pinfunction "1_8") (pintype "passive"))
      (node (ref "X5") (pin "3") (pinfunction "1_3") (pintype "passive"))
      (node (ref "X6") (pin "3") (pinfunction "1_3") (pintype "passive"))
      (node (ref "X7") (pin "3") (pinfunction "1_3") (pintype "passive"))
    )
    (net (code "60") (name "~{RESET}") (class "Default")
      (node (ref "X4") (pin "6") (pinfunction "1_6") (pintype "passive"))
      (node (ref "X5") (pin "4") (pinfunction "1_4") (pintype "passive"))
      (node (ref "X6") (pin "4") (pinfunction "1_4") (pintype "passive"))
      (node (ref "X7") (pin "4") (pinfunction "1_4") (pintype "passive"))
    )
  )
)
